# Interface.net
KiCad netlist of a schematic drawn in Altium Designer
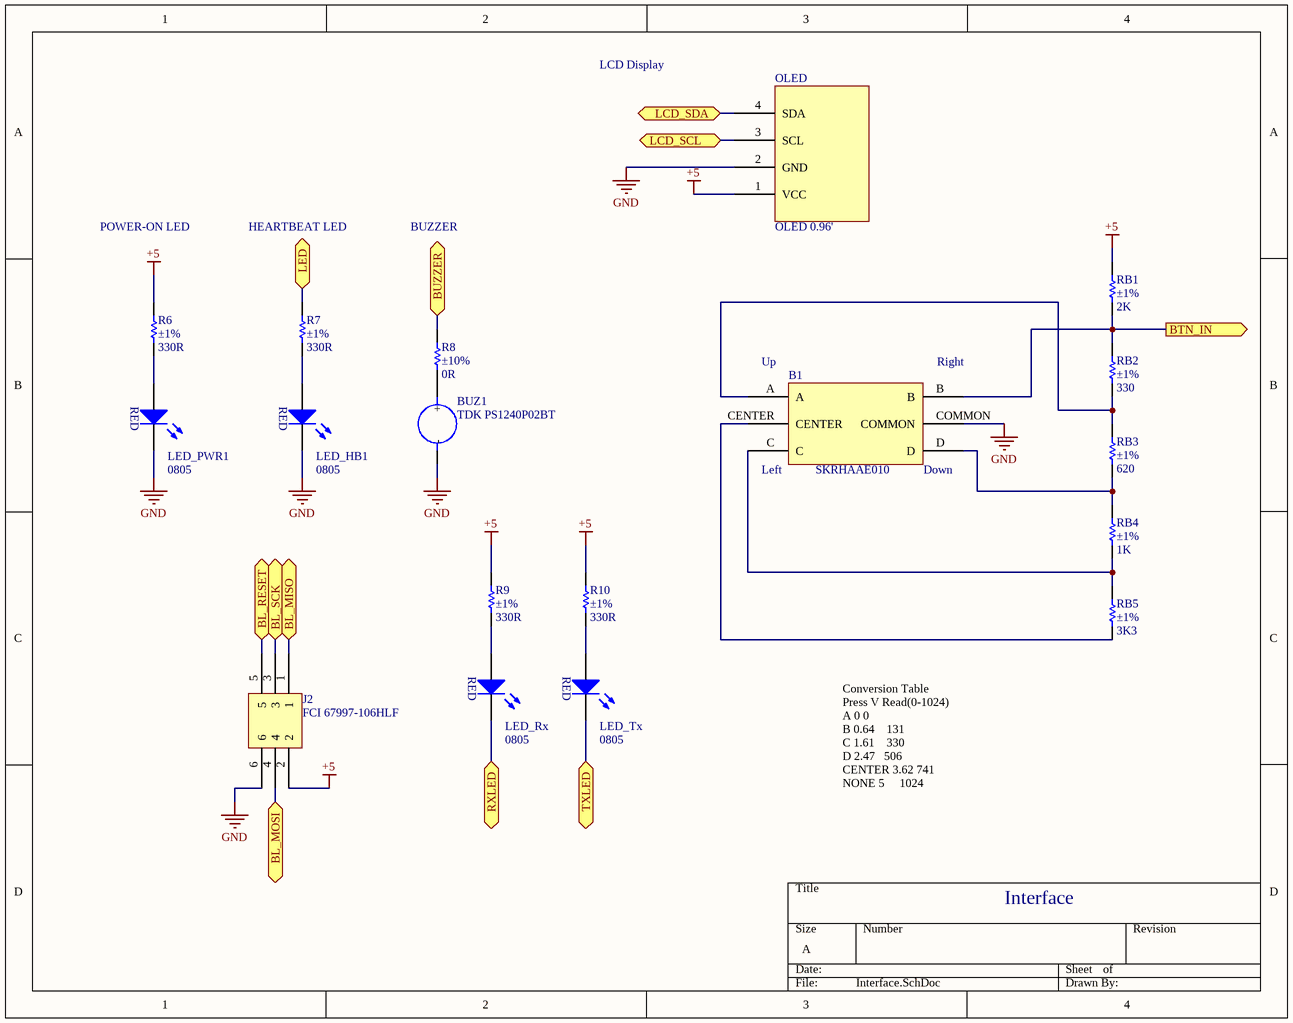
[diagram p0: Interface.SchDoc]

(export (version "E")
  (design (tool "Eeschema 10.0.6"))
  (components
    (comp (ref "B1")
      (value "SKRHAAE010")
      (footprint "PCB-uddfpa39w3pawwu0f32n-1")
      (description "TACT switch 4-direction with Center-Push Function (Surface Mount)")
      (libsource (lib "CommunityVault") (part "SYM-0t5k0v9upau5edea4oo5-1"))
    )
    (comp (ref "BUZ1")
      (value "TDK PS1240P02BT")
      (footprint "2P-7.6-D12X6.5H")
      (description "Audio Indicator Buzzer Piezo 3Vo-p Pin Through Hole")
      (fields (field (name "MANUFACTURER PART NUMBER") "PS1240P02BT"))
      (libsource (lib "Octopart library") (part "TDK-PS1240P02BT-2"))
    )
    (comp (ref "J2")
      (value "FCI 67997-106HLF")
      (footprint "PCB-94q9r8plw7fzhg0k9c12-1")
      (description "Conn; Rect; Header; Unshrouded; 6 Pos; 2.54mm Pitch; 2-Row; Thru-Hole; BergStik")
      (fields (field (name "MANUFACTURER PART NUMBER") "67997-106HLF"))
      (libsource (lib "CommunityVault") (part "CMP-c8f30399bb8b1734-1"))
    )
    (comp (ref "LED_HB1")
      (value "CMP-7f15b6173d91a0d2-5")
      (footprint "LED0805")
      (description "LED; SMD; 0805; red; 7.2-17mcd; 2x1.25mm; 170°; 1.8÷2.6V; 20mA")
      (fields (field (name "CASE/PACKAGE") "0805") (field (name "MANUFACTURER PART NUMBER") "HSMH-C170"))
      (libsource (lib "CommunityVault") (part "CMP-7f15b6173d91a0d2-5"))
    )
    (comp (ref "LED_PWR1")
      (value "CMP-7f15b6173d91a0d2-5")
      (footprint "LED0805")
      (description "LED; SMD; 0805; red; 7.2-17mcd; 2x1.25mm; 170°; 1.8÷2.6V; 20mA")
      (fields (field (name "CASE/PACKAGE") "0805") (field (name "MANUFACTURER PART NUMBER") "HSMH-C170"))
      (libsource (lib "CommunityVault") (part "CMP-7f15b6173d91a0d2-5"))
    )
    (comp (ref "LED_Rx")
      (value "CMP-7f15b6173d91a0d2-5")
      (footprint "LED0805")
      (description "LED; SMD; 0805; red; 7.2-17mcd; 2x1.25mm; 170°; 1.8÷2.6V; 20mA")
      (fields (field (name "CASE/PACKAGE") "0805") (field (name "MANUFACTURER PART NUMBER") "HSMH-C170"))
      (libsource (lib "CommunityVault") (part "CMP-7f15b6173d91a0d2-5"))
    )
    (comp (ref "LED_Tx")
      (value "CMP-7f15b6173d91a0d2-5")
      (footprint "LED0805")
      (description "LED; SMD; 0805; red; 7.2-17mcd; 2x1.25mm; 170°; 1.8÷2.6V; 20mA")
      (fields (field (name "CASE/PACKAGE") "0805") (field (name "MANUFACTURER PART NUMBER") "HSMH-C170"))
      (libsource (lib "CommunityVault") (part "CMP-7f15b6173d91a0d2-5"))
    )
    (comp (ref "OLED")
      (value "OLED 0.96'")
      (footprint "PCBComponent_1 - duplicate")
      (description "0.96' oled i2c screen")
      (libsource (lib "CommunityVault") (part "CMP-am4xhbx8j6fw9q56sa5u-8"))
    )
    (comp (ref "R6")
      (value "Bourns CR0805-FX-4701GLF")
      (footprint "PCB-4097432-1")
      (description "Res Thick Film 0805 4.7K Ohm 1% 1/8W ±100ppm/°C Molded SMD SMD Paper Tape on Plastic Reel")
      (fields
        (field (name "MANUFACTURER PART NUMBER") "CR0805-FX-4701GLF")
        (field (name "RESISTANCE TOLERANCE") "±1%")
        (field (name "RESISTANCE") "330R")
      )
      (libsource (lib "CommunityVault") (part "CMP-97505e06006c4897-1"))
    )
    (comp (ref "R7")
      (value "Bourns CR0805-FX-4701GLF")
      (footprint "PCB-4097432-1")
      (description "Res Thick Film 0805 4.7K Ohm 1% 1/8W ±100ppm/°C Molded SMD SMD Paper Tape on Plastic Reel")
      (fields
        (field (name "MANUFACTURER PART NUMBER") "CR0805-FX-4701GLF")
        (field (name "RESISTANCE TOLERANCE") "±1%")
        (field (name "RESISTANCE") "330R")
      )
      (libsource (lib "CommunityVault") (part "CMP-97505e06006c4897-1"))
    )
    (comp (ref "R8")
      (value "Bourns CR0805-FX-4701GLF")
      (footprint "PCB-4097432-1")
      (description "Res Thick Film 0805 4.7K Ohm 1% 1/8W ±100ppm/°C Molded SMD SMD Paper Tape on Plastic Reel")
      (fields
        (field (name "MANUFACTURER PART NUMBER") "CR0805-FX-4701GLF")
        (field (name "RESISTANCE TOLERANCE") "±10%")
        (field (name "RESISTANCE") "0R")
      )
      (libsource (lib "CommunityVault") (part "CMP-97505e06006c4897-1"))
    )
    (comp (ref "R9")
      (value "Bourns CR0805-FX-4701GLF")
      (footprint "PCB-4097432-1")
      (description "Res Thick Film 0805 4.7K Ohm 1% 1/8W ±100ppm/°C Molded SMD SMD Paper Tape on Plastic Reel")
      (fields
        (field (name "MANUFACTURER PART NUMBER") "CR0805-FX-4701GLF")
        (field (name "RESISTANCE TOLERANCE") "±1%")
        (field (name "RESISTANCE") "330R")
      )
      (libsource (lib "CommunityVault") (part "CMP-97505e06006c4897-1"))
    )
    (comp (ref "R10")
      (value "Bourns CR0805-FX-4701GLF")
      (footprint "PCB-4097432-1")
      (description "Res Thick Film 0805 4.7K Ohm 1% 1/8W ±100ppm/°C Molded SMD SMD Paper Tape on Plastic Reel")
      (fields
        (field (name "MANUFACTURER PART NUMBER") "CR0805-FX-4701GLF")
        (field (name "RESISTANCE TOLERANCE") "±1%")
        (field (name "RESISTANCE") "330R")
      )
      (libsource (lib "CommunityVault") (part "CMP-97505e06006c4897-1"))
    )
    (comp (ref "RB1")
      (value "Bourns CR0805-FX-4701GLF")
      (footprint "PCB-4097432-1")
      (description "Res Thick Film 0805 4.7K Ohm 1% 1/8W ±100ppm/°C Molded SMD SMD Paper Tape on Plastic Reel")
      (fields
        (field (name "MANUFACTURER PART NUMBER") "CR0805-FX-4701GLF")
        (field (name "RESISTANCE TOLERANCE") "±1%")
        (field (name "RESISTANCE") "2K")
      )
      (libsource (lib "CommunityVault") (part "CMP-97505e06006c4897-1"))
    )
    (comp (ref "RB2")
      (value "Bourns CR0805-FX-4701GLF")
      (footprint "PCB-4097432-1")
      (description "Res Thick Film 0805 4.7K Ohm 1% 1/8W ±100ppm/°C Molded SMD SMD Paper Tape on Plastic Reel")
      (fields
        (field (name "MANUFACTURER PART NUMBER") "CR0805-FX-4701GLF")
        (field (name "RESISTANCE TOLERANCE") "±1%")
        (field (name "RESISTANCE") "330")
      )
      (libsource (lib "CommunityVault") (part "CMP-97505e06006c4897-1"))
    )
    (comp (ref "RB3")
      (value "Bourns CR0805-FX-4701GLF")
      (footprint "PCB-4097432-1")
      (description "Res Thick Film 0805 4.7K Ohm 1% 1/8W ±100ppm/°C Molded SMD SMD Paper Tape on Plastic Reel")
      (fields
        (field (name "MANUFACTURER PART NUMBER") "CR0805-FX-4701GLF")
        (field (name "RESISTANCE TOLERANCE") "±1%")
        (field (name "RESISTANCE") "620")
      )
      (libsource (lib "CommunityVault") (part "CMP-97505e06006c4897-1"))
    )
    (comp (ref "RB4")
      (value "Bourns CR0805-FX-4701GLF")
      (footprint "PCB-4097432-1")
      (description "Res Thick Film 0805 4.7K Ohm 1% 1/8W ±100ppm/°C Molded SMD SMD Paper Tape on Plastic Reel")
      (fields
        (field (name "MANUFACTURER PART NUMBER") "CR0805-FX-4701GLF")
        (field (name "RESISTANCE TOLERANCE") "±1%")
        (field (name "RESISTANCE") "1K")
      )
      (libsource (lib "CommunityVault") (part "CMP-97505e06006c4897-1"))
    )
    (comp (ref "RB5")
      (value "Bourns CR0805-FX-4701GLF")
      (footprint "PCB-4097432-1")
      (description "Res Thick Film 0805 4.7K Ohm 1% 1/8W ±100ppm/°C Molded SMD SMD Paper Tape on Plastic Reel")
      (fields
        (field (name "MANUFACTURER PART NUMBER") "CR0805-FX-4701GLF")
        (field (name "RESISTANCE TOLERANCE") "±1%")
        (field (name "RESISTANCE") "3K3")
      )
      (libsource (lib "CommunityVault") (part "CMP-97505e06006c4897-1"))
    )
  )
  (nets
    (net (code "1") (name "+5") (class "Default")
      (node (ref "J2") (pin "2") (pinfunction "2_2") (pintype "passive"))
      (node (ref "OLED") (pin "1") (pinfunction "VCC_1") (pintype "passive"))
      (node (ref "R10") (pin "2") (pinfunction "2_2") (pintype "passive"))
      (node (ref "R6") (pin "2") (pinfunction "2_2") (pintype "passive"))
      (node (ref "R9") (pin "2") (pinfunction "2_2") (pintype "passive"))
      (node (ref "RB1") (pin "2") (pinfunction "2_2") (pintype "passive"))
    )
    (net (code "2") (name "/BL_MISO") (class "Default")
      (node (ref "J2") (pin "1") (pinfunction "1_1") (pintype "passive"))
    )
    (net (code "3") (name "/BL_MOSI") (class "Default")
      (node (ref "J2") (pin "4") (pinfunction "4_4") (pintype "passive"))
    )
    (net (code "4") (name "/BL_RESET") (class "Default")
      (node (ref "J2") (pin "5") (pinfunction "5_5") (pintype "passive"))
    )
    (net (code "5") (name "/BL_SCK") (class "Default")
      (node (ref "J2") (pin "3") (pinfunction "3_3") (pintype "passive"))
    )
    (net (code "6") (name "/BTN_IN") (class "Default")
      (node (ref "B1") (pin "B") (pinfunction "B_B") (pintype "passive"))
      (node (ref "RB1") (pin "1") (pinfunction "1_1") (pintype "passive"))
      (node (ref "RB2") (pin "2") (pinfunction "2_2") (pintype "passive"))
    )
    (net (code "7") (name "/BUZZER") (class "Default")
      (node (ref "R8") (pin "2") (pinfunction "2_2") (pintype "passive"))
    )
    (net (code "8") (name "/LCD_SCL") (class "Default")
      (node (ref "OLED") (pin "3") (pinfunction "SCL_3") (pintype "passive"))
    )
    (net (code "9") (name "/LCD_SDA") (class "Default")
      (node (ref "OLED") (pin "4") (pinfunction "SDA_4") (pintype "passive"))
    )
    (net (code "10") (name "/LED") (class "Default")
      (node (ref "R7") (pin "2") (pinfunction "2_2") (pintype "passive"))
    )
    (net (code "11") (name "/RXLED") (class "Default")
      (node (ref "LED_Rx") (pin "1") (pinfunction "K_1") (pintype "passive"))
    )
    (net (code "12") (name "/TXLED") (class "Default")
      (node (ref "LED_Tx") (pin "1") (pinfunction "K_1") (pintype "passive"))
    )
    (net (code "13") (name "GND") (class "Default")
      (node (ref "B1") (pin "COMMON") (pinfunction "COMMON_COMMON") (pintype "passive"))
      (node (ref "BUZ1") (pin "-") (pinfunction "-_-") (pintype "passive"))
      (node (ref "J2") (pin "6") (pinfunction "6_6") (pintype "passive"))
      (node (ref "LED_HB1") (pin "1") (pinfunction "K_1") (pintype "passive"))
      (node (ref "LED_PWR1") (pin "1") (pinfunction "K_1") (pintype "passive"))
      (node (ref "OLED") (pin "2") (pinfunction "GND_2") (pintype "passive"))
    )
    (net (code "14") (name "Net-(B1-PadA)") (class "Default")
      (node (ref "B1") (pin "A") (pinfunction "A_A") (pintype "passive"))
      (node (ref "RB2") (pin "1") (pinfunction "1_1") (pintype "passive"))
      (node (ref "RB3") (pin "2") (pinfunction "2_2") (pintype "passive"))
    )
    (net (code "15") (name "Net-(B1-PadC)") (class "Default")
      (node (ref "B1") (pin "C") (pinfunction "C_C") (pintype "passive"))
      (node (ref "RB4") (pin "1") (pinfunction "1_1") (pintype "passive"))
      (node (ref "RB5") (pin "2") (pinfunction "2_2") (pintype "passive"))
    )
    (net (code "16") (name "Net-(B1-PadCENTER)") (class "Default")
      (node (ref "B1") (pin "CENTER") (pinfunction "CENTER_CENTER") (pintype "passive"))
      (node (ref "RB5") (pin "1") (pinfunction "1_1") (pintype "passive"))
    )
    (net (code "17") (name "Net-(B1-PadD)") (class "Default")
      (node (ref "B1") (pin "D") (pinfunction "D_D") (pintype "passive"))
      (node (ref "RB3") (pin "1") (pinfunction "1_1") (pintype "passive"))
      (node (ref "RB4") (pin "2") (pinfunction "2_2") (pintype "passive"))
    )
    (net (code "18") (name "Net-(BUZ1-Pad+)") (class "Default")
      (node (ref "BUZ1") (pin "+") (pinfunction "+_+") (pintype "passive"))
      (node (ref "R8") (pin "1") (pinfunction "1_1") (pintype "passive"))
    )
    (net (code "19") (name "Net-(LED_HB1-A)") (class "Default")
      (node (ref "LED_HB1") (pin "2") (pinfunction "A_2") (pintype "passive"))
      (node (ref "R7") (pin "1") (pinfunction "1_1") (pintype "passive"))
    )
    (net (code "20") (name "Net-(LED_PWR1-A)") (class "Default")
      (node (ref "LED_PWR1") (pin "2") (pinfunction "A_2") (pintype "passive"))
      (node (ref "R6") (pin "1") (pinfunction "1_1") (pintype "passive"))
    )
    (net (code "21") (name "Net-(LED_Rx-A)") (class "Default")
      (node (ref "LED_Rx") (pin "2") (pinfunction "A_2") (pintype "passive"))
      (node (ref "R9") (pin "1") (pinfunction "1_1") (pintype "passive"))
    )
    (net (code "22") (name "Net-(LED_Tx-A)") (class "Default")
      (node (ref "LED_Tx") (pin "2") (pinfunction "A_2") (pintype "passive"))
      (node (ref "R10") (pin "1") (pinfunction "1_1") (pintype "passive"))
    )
  )
)
